# Fri3D_2020_Power.net
KiCad netlist of a schematic drawn in Altium Designer
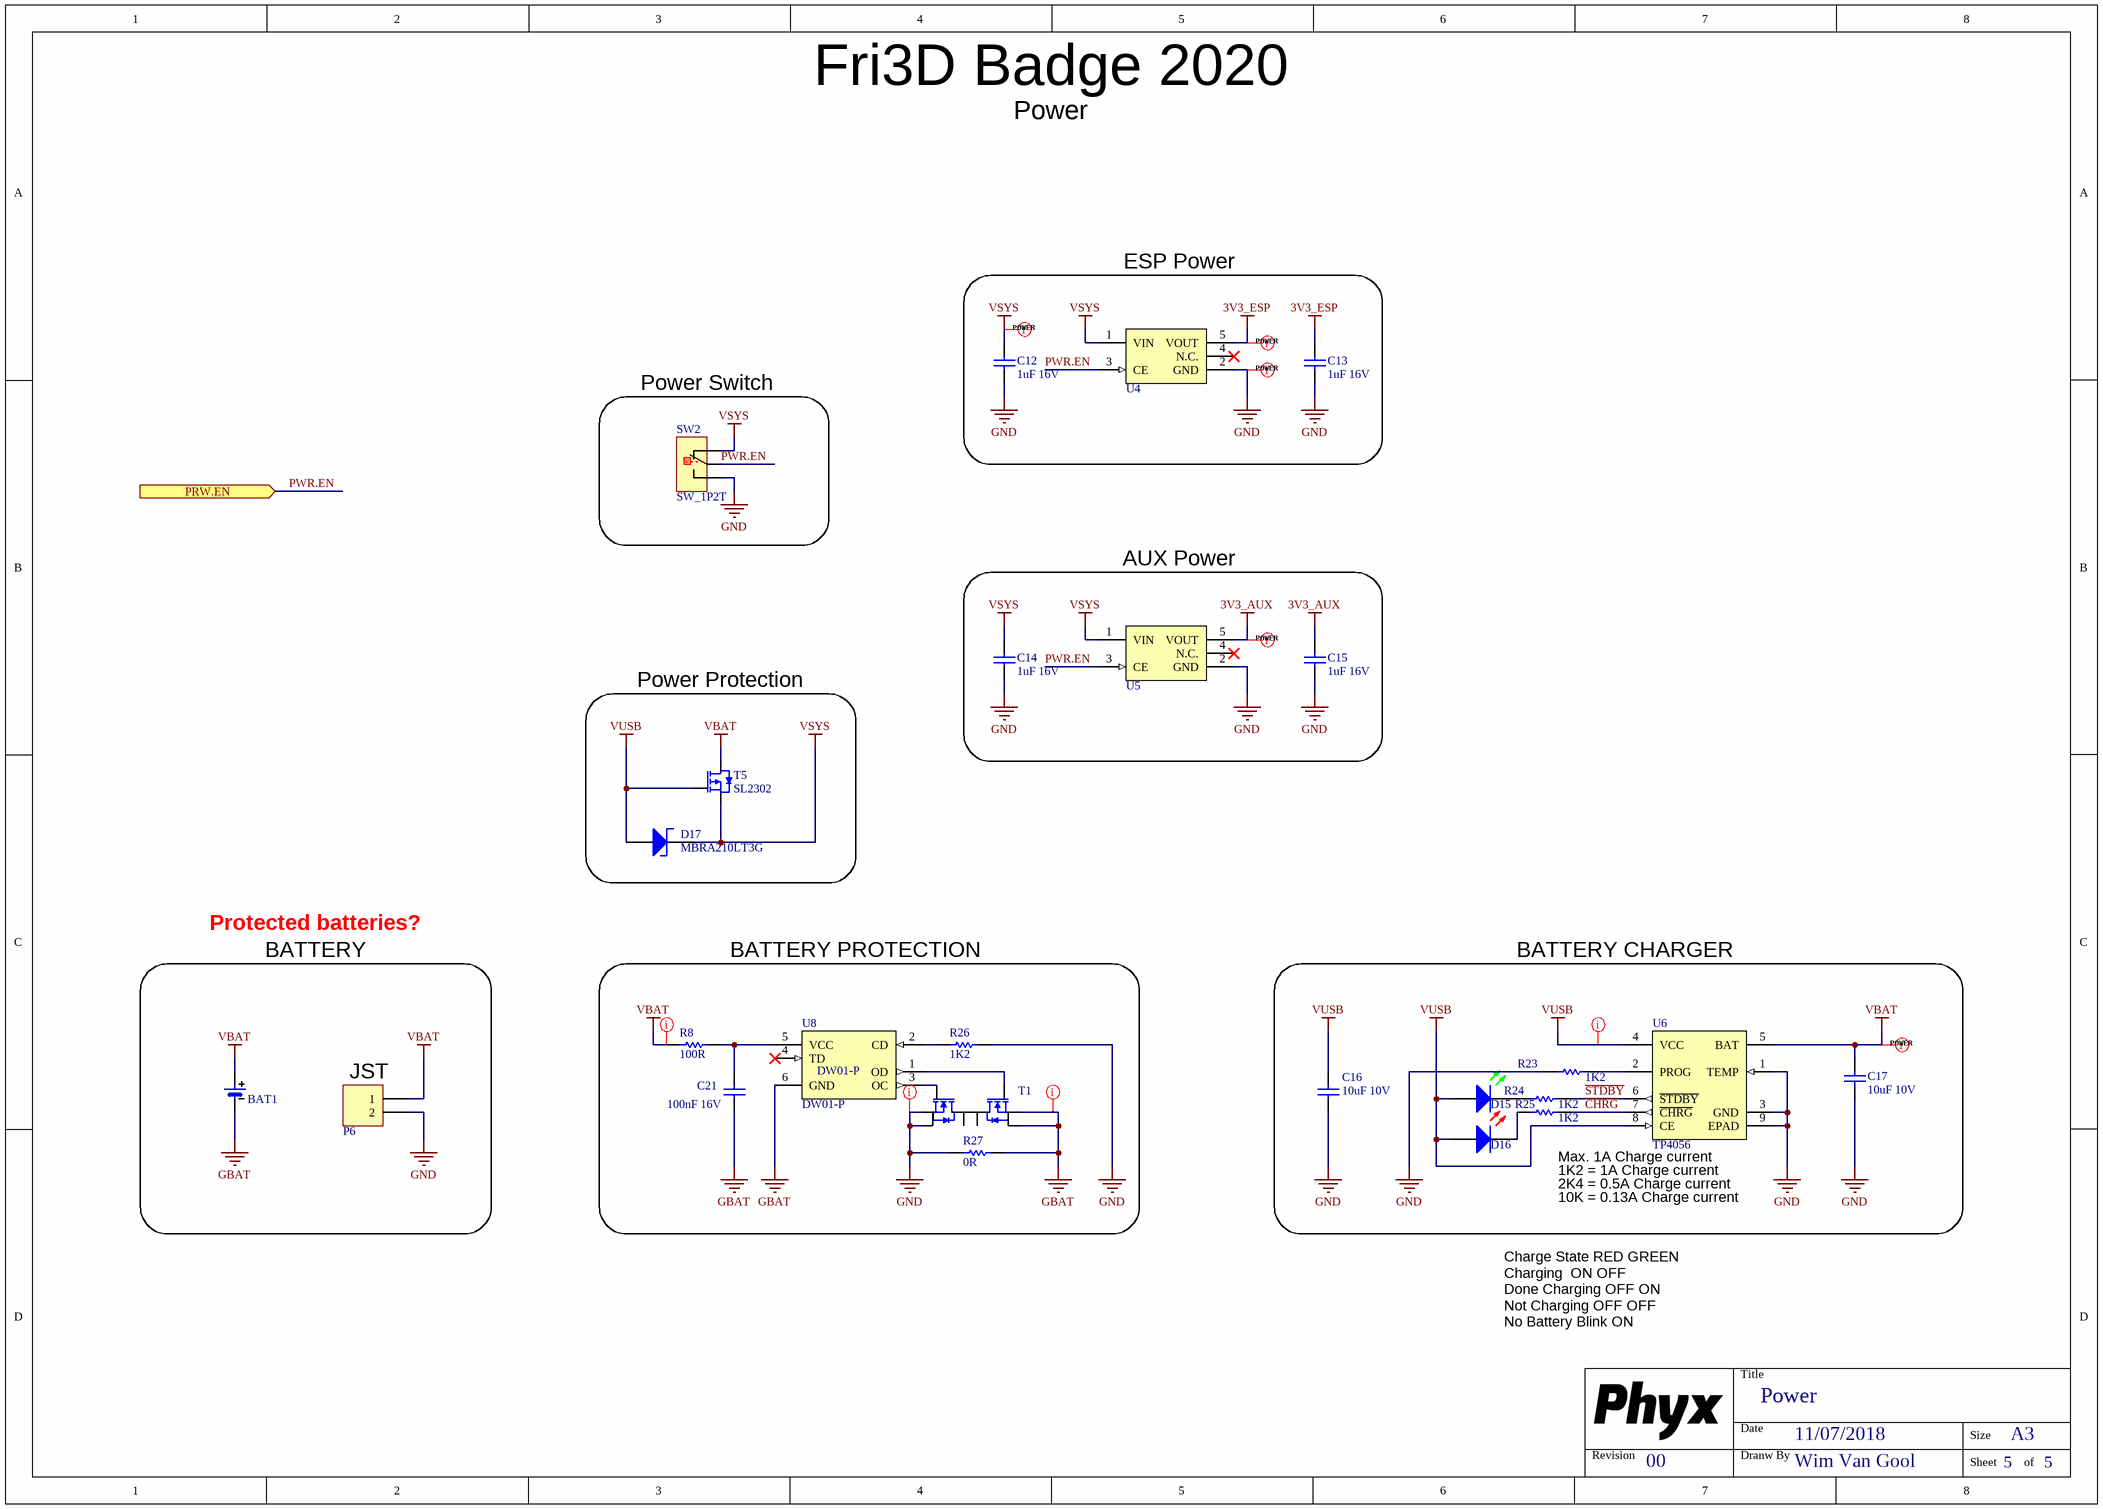
[diagram p0: Fri3D_2020_Power.SchDoc]

(export (version "E")
  (design (tool "Eeschema 10.0.6"))
  (components
    (comp (ref "BAT1")
      (value "18650 Battery holder with spring")
      (footprint "BAT_18650_SPRING")
      (description "=Description")
      (libsource (lib "Phyx_Components") (part "BAT_2"))
    )
    (comp (ref "C12")
      (value "1uF 16V")
      (footprint "C0603_N")
      (description "Capacitor Ceramic")
      (fields (field (name "Comment") "CAP_CERAMIC"))
      (libsource (lib "Phyx_Components") (part "CAP_CERAMIC"))
    )
    (comp (ref "C13")
      (value "1uF 16V")
      (footprint "C0603_N")
      (description "Capacitor Ceramic")
      (fields (field (name "Comment") "CAP_CERAMIC"))
      (libsource (lib "Phyx_Components") (part "CAP_CERAMIC"))
    )
    (comp (ref "C14")
      (value "1uF 16V")
      (footprint "C0603_N")
      (description "Capacitor Ceramic")
      (fields (field (name "Comment") "CAP_CERAMIC"))
      (libsource (lib "Phyx_Components") (part "CAP_CERAMIC"))
    )
    (comp (ref "C15")
      (value "1uF 16V")
      (footprint "C0603_N")
      (description "Capacitor Ceramic")
      (fields (field (name "Comment") "CAP_CERAMIC"))
      (libsource (lib "Phyx_Components") (part "CAP_CERAMIC"))
    )
    (comp (ref "C16")
      (value "10uF 10V")
      (footprint "C0805_N")
      (description "Capacitor Ceramic")
      (fields (field (name "Comment") "CAP_CERAMIC"))
      (libsource (lib "Phyx_Components") (part "CAP_CERAMIC"))
    )
    (comp (ref "C17")
      (value "10uF 10V")
      (footprint "C0805_N")
      (description "Capacitor Ceramic")
      (fields (field (name "Comment") "CAP_CERAMIC"))
      (libsource (lib "Phyx_Components") (part "CAP_CERAMIC"))
    )
    (comp (ref "C21")
      (value "100nF 16V")
      (footprint "C0603_N")
      (description "Capacitor Ceramic")
      (libsource (lib "Phyx_Components") (part "CAP_CERAMIC"))
    )
    (comp (ref "D15")
      (value "Default 0805 Green LED")
      (footprint "LED_0805_GR")
      (description "=Description")
      (libsource (lib "Phyx_Components") (part "LED_GREEN"))
    )
    (comp (ref "D16")
      (value "Default 0805 Red LED")
      (footprint "LED_0805_RD")
      (description "=Description")
      (libsource (lib "Phyx_Components") (part "LED_RED"))
    )
    (comp (ref "D17")
      (value "MBRA210LT3G")
      (footprint "SMA_AC")
      (description "=Description")
      (libsource (lib "Phyx_Components") (part "Schottky_AC"))
    )
    (comp (ref "P6")
      (value "Header 2.0mm Shrouded 2")
      (footprint "WE_620102131822")
      (libsource (lib "Phyx_Components") (part "Header 2"))
    )
    (comp (ref "R8")
      (value "100R")
      (footprint "R0603_N")
      (fields (field (name "Comment") "RESISTOR"))
      (libsource (lib "Phyx_Components") (part "RESISTOR"))
    )
    (comp (ref "R23")
      (value "1K2")
      (footprint "R0603_N")
      (fields (field (name "Comment") "RESISTOR"))
      (libsource (lib "Phyx_Components") (part "RESISTOR"))
    )
    (comp (ref "R24")
      (value "1K2")
      (footprint "R0603_N")
      (fields (field (name "Comment") "RESISTOR"))
      (libsource (lib "Phyx_Components") (part "RESISTOR"))
    )
    (comp (ref "R25")
      (value "1K2")
      (footprint "R0603_N")
      (fields (field (name "Comment") "RESISTOR"))
      (libsource (lib "Phyx_Components") (part "RESISTOR"))
    )
    (comp (ref "R26")
      (value "1K2")
      (footprint "R0603_N")
      (fields (field (name "Comment") "RESISTOR"))
      (libsource (lib "Phyx_Components") (part "RESISTOR"))
    )
    (comp (ref "R27")
      (value "0R")
      (footprint "R0603_N")
      (libsource (lib "Phyx_Components") (part "RESISTOR"))
    )
    (comp (ref "SW2")
      (value "SW_1P2T")
      (footprint "WE_450404015514")
      (libsource (lib "Phyx_Components") (part "SW_1P2T"))
    )
    (comp (ref "T1")
      (value "Dual N-Ch MOSFET Common Drain")
      (footprint "TSSOP_8_65P")
      (description "=Description")
      (libsource (lib "Phyx_Components") (part "N_MOSFET_FS8205A"))
    )
    (comp (ref "T5")
      (value "SL2302")
      (footprint "SOT23-3")
      (description "=Description")
      (libsource (lib "Phyx_Components") (part "P_MOSFET_GSD"))
    )
    (comp (ref "U4")
      (value "3V3 LDO 700mA 50mV")
      (footprint "SOT23-5")
      (description "=Designator")
      (libsource (lib "Phyx_Components") (part "XC6210_SOT"))
    )
    (comp (ref "U5")
      (value "3V3 LDO 700mA 50mV")
      (footprint "SOT23-5")
      (description "=Designator")
      (libsource (lib "Phyx_Components") (part "XC6210_SOT"))
    )
    (comp (ref "U6")
      (value "TP4056")
      (footprint "SOIC_N_8_TH")
      (description "=Description")
      (fields (field (name "Comment") "Single Cell LiIon charger max 1A"))
      (libsource (lib "Phyx_Components") (part "TP4056"))
    )
    (comp (ref "U8")
      (value "DW01-P")
      (footprint "SOT23-6")
      (description "=Description")
      (fields (field (name "Comment") "DW01-P single cell lithium protection"))
      (libsource (lib "Phyx_Components") (part "DW01-P"))
    )
  )
  (nets
    (net (code "1") (name "/PWR.EN") (class "Default")
      (node (ref "SW2") (pin "2") (pinfunction "2_2") (pintype "passive"))
      (node (ref "U4") (pin "3") (pinfunction "CE_3") (pintype "input"))
      (node (ref "U5") (pin "3") (pinfunction "CE_3") (pintype "input"))
    )
    (net (code "2") (name "/~{CHRG}") (class "Default")
      (node (ref "R25") (pin "2") (pinfunction "2_2") (pintype "passive"))
      (node (ref "U6") (pin "7") (pinfunction "~{CHRG}_7") (pintype "output"))
    )
    (net (code "3") (name "/~{STDBY}") (class "Default")
      (node (ref "R24") (pin "2") (pinfunction "2_2") (pintype "passive"))
      (node (ref "U6") (pin "6") (pinfunction "~{STDBY}_6") (pintype "output"))
    )
    (net (code "4") (name "3V3_AUX") (class "Default")
      (node (ref "C15") (pin "1") (pinfunction "1_1") (pintype "passive"))
      (node (ref "U5") (pin "5") (pinfunction "VOUT_5") (pintype "power_in"))
    )
    (net (code "5") (name "3V3_ESP") (class "Default")
      (node (ref "C13") (pin "1") (pinfunction "1_1") (pintype "passive"))
      (node (ref "U4") (pin "5") (pinfunction "VOUT_5") (pintype "power_in"))
    )
    (net (code "6") (name "GBAT") (class "Default")
      (node (ref "BAT1") (pin "2") (pinfunction "2_2") (pintype "passive"))
      (node (ref "C21") (pin "2") (pinfunction "2_2") (pintype "passive"))
      (node (ref "R27") (pin "1") (pinfunction "1_1") (pintype "passive"))
      (node (ref "T1") (pin "2") (pinfunction "S1_2") (pintype "passive"))
      (node (ref "T1") (pin "3") (pinfunction "S1_3") (pintype "passive"))
      (node (ref "U8") (pin "6") (pinfunction "GND_6") (pintype "power_in"))
    )
    (net (code "7") (name "GND") (class "Default")
      (node (ref "C12") (pin "2") (pinfunction "2_2") (pintype "passive"))
      (node (ref "C13") (pin "2") (pinfunction "2_2") (pintype "passive"))
      (node (ref "C14") (pin "2") (pinfunction "2_2") (pintype "passive"))
      (node (ref "C15") (pin "2") (pinfunction "2_2") (pintype "passive"))
      (node (ref "C16") (pin "2") (pinfunction "2_2") (pintype "passive"))
      (node (ref "C17") (pin "2") (pinfunction "2_2") (pintype "passive"))
      (node (ref "P6") (pin "2") (pinfunction "2_2") (pintype "passive"))
      (node (ref "R23") (pin "2") (pinfunction "2_2") (pintype "passive"))
      (node (ref "R26") (pin "2") (pinfunction "2_2") (pintype "passive"))
      (node (ref "R27") (pin "2") (pinfunction "2_2") (pintype "passive"))
      (node (ref "SW2") (pin "3") (pinfunction "3_3") (pintype "passive"))
      (node (ref "T1") (pin "6") (pinfunction "S2_6") (pintype "passive"))
      (node (ref "T1") (pin "7") (pinfunction "S2_7") (pintype "passive"))
      (node (ref "U4") (pin "2") (pinfunction "GND_2") (pintype "power_in"))
      (node (ref "U5") (pin "2") (pinfunction "GND_2") (pintype "power_in"))
      (node (ref "U6") (pin "1") (pinfunction "TEMP_1") (pintype "input"))
      (node (ref "U6") (pin "3") (pinfunction "GND_3") (pintype "power_in"))
      (node (ref "U6") (pin "9") (pinfunction "EPAD_9") (pintype "power_in"))
    )
    (net (code "8") (name "Net-(D15-K)") (class "Default")
      (node (ref "D15") (pin "2") (pinfunction "K_2") (pintype "passive"))
      (node (ref "R24") (pin "1") (pinfunction "1_1") (pintype "passive"))
    )
    (net (code "9") (name "Net-(D16-K)") (class "Default")
      (node (ref "D16") (pin "2") (pinfunction "K_2") (pintype "passive"))
      (node (ref "R25") (pin "1") (pinfunction "1_1") (pintype "passive"))
    )
    (net (code "10") (name "Net-(T1-G1)") (class "Default")
      (node (ref "T1") (pin "4") (pinfunction "G1_4") (pintype "passive"))
      (node (ref "U8") (pin "1") (pinfunction "OD_1") (pintype "output"))
    )
    (net (code "11") (name "Net-(T1-G2)") (class "Default")
      (node (ref "T1") (pin "5") (pinfunction "G2_5") (pintype "passive"))
      (node (ref "U8") (pin "3") (pinfunction "OC_3") (pintype "output"))
    )
    (net (code "12") (name "Net-(U6-PROG)") (class "Default")
      (node (ref "R23") (pin "1") (pinfunction "1_1") (pintype "passive"))
      (node (ref "U6") (pin "2") (pinfunction "PROG_2") (pintype "passive"))
    )
    (net (code "13") (name "Net-(U8-CD)") (class "Default")
      (node (ref "R26") (pin "1") (pinfunction "1_1") (pintype "passive"))
      (node (ref "U8") (pin "2") (pinfunction "CD_2") (pintype "input"))
    )
    (net (code "14") (name "Net-(U8-VCC)") (class "Default")
      (node (ref "C21") (pin "1") (pinfunction "1_1") (pintype "passive"))
      (node (ref "R8") (pin "2") (pinfunction "2_2") (pintype "passive"))
      (node (ref "U8") (pin "5") (pinfunction "VCC_5") (pintype "power_in"))
    )
    (net (code "15") (name "VBAT") (class "Default")
      (node (ref "BAT1") (pin "1") (pinfunction "1_1") (pintype "passive"))
      (node (ref "C17") (pin "1") (pinfunction "1_1") (pintype "passive"))
      (node (ref "P6") (pin "1") (pinfunction "1_1") (pintype "passive"))
      (node (ref "R8") (pin "1") (pinfunction "1_1") (pintype "passive"))
      (node (ref "T5") (pin "3") (pinfunction "D_3") (pintype "passive"))
      (node (ref "U6") (pin "5") (pinfunction "BAT_5") (pintype "power_in"))
    )
    (net (code "16") (name "VSYS") (class "Default")
      (node (ref "C12") (pin "1") (pinfunction "1_1") (pintype "passive"))
      (node (ref "C14") (pin "1") (pinfunction "1_1") (pintype "passive"))
      (node (ref "D17") (pin "C") (pinfunction "C_C") (pintype "passive"))
      (node (ref "SW2") (pin "1") (pinfunction "1_1") (pintype "passive"))
      (node (ref "T5") (pin "2") (pinfunction "S_2") (pintype "passive"))
      (node (ref "U4") (pin "1") (pinfunction "VIN_1") (pintype "power_in"))
      (node (ref "U5") (pin "1") (pinfunction "VIN_1") (pintype "power_in"))
    )
    (net (code "17") (name "VUSB") (class "Default")
      (node (ref "C16") (pin "1") (pinfunction "1_1") (pintype "passive"))
      (node (ref "D15") (pin "1") (pinfunction "A_1") (pintype "passive"))
      (node (ref "D16") (pin "1") (pinfunction "A_1") (pintype "passive"))
      (node (ref "D17") (pin "A") (pinfunction "A_A") (pintype "passive"))
      (node (ref "T5") (pin "1") (pinfunction "G_1") (pintype "passive"))
      (node (ref "U6") (pin "4") (pinfunction "VCC_4") (pintype "power_in"))
      (node (ref "U6") (pin "8") (pinfunction "CE_8") (pintype "input"))
    )
    (net (code "18") (name "unconnected-(T1-D1-Pad1)") (class "Default")
      (node (ref "T1") (pin "1") (pinfunction "D1_1") (pintype "passive"))
    )
    (net (code "19") (name "unconnected-(T1-D2-Pad8)") (class "Default")
      (node (ref "T1") (pin "8") (pinfunction "D2_8") (pintype "passive"))
    )
    (net (code "20") (name "unconnected-(U4-N.C.-Pad4)") (class "Default")
      (node (ref "U4") (pin "4") (pinfunction "N.C._4") (pintype "passive+no_connect"))
    )
    (net (code "21") (name "unconnected-(U5-N.C.-Pad4)") (class "Default")
      (node (ref "U5") (pin "4") (pinfunction "N.C._4") (pintype "passive+no_connect"))
    )
    (net (code "22") (name "unconnected-(U8-TD-Pad4)") (class "Default")
      (node (ref "U8") (pin "4") (pinfunction "TD_4") (pintype "input+no_connect"))
    )
  )
)
